# 2.net
KiCad netlist of a schematic drawn in Altium Designer
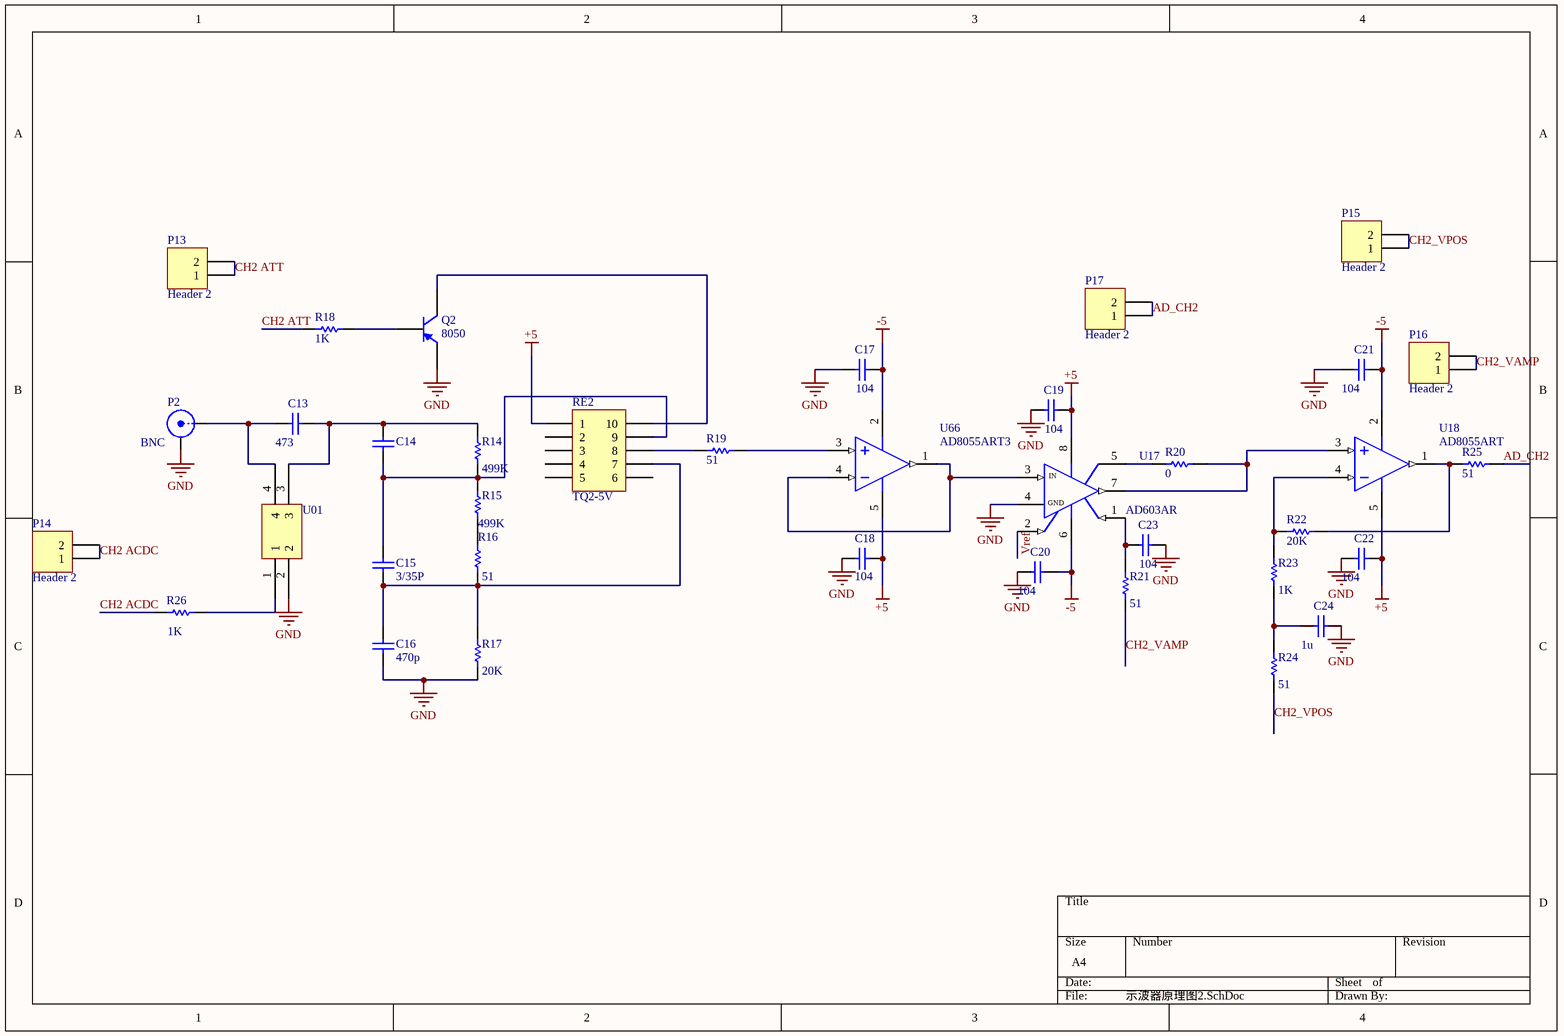
[diagram p0: 示波器原理图2.SchDoc]

(export (version "E")
  (design (tool "Eeschema 10.0.6"))
  (components
    (comp (ref "C13")
      (value "473")
      (footprint "0805封装:PCBComponent_1")
      (description "Capacitor")
      (fields (field (name "PUBLISHER") "Altium Limited"))
      (libsource (lib "Miscellaneous Devices") (part "Cap"))
    )
    (comp (ref "C14")
      (value "~")
      (footprint "0805封装:PCBComponent_1")
      (description "Capacitor")
      (fields (field (name "PUBLISHER") "Altium Limited"))
      (libsource (lib "Miscellaneous Devices") (part "Cap"))
    )
    (comp (ref "C15")
      (value "3/35P")
      (footprint "0805封装:PCBComponent_1")
      (description "Capacitor")
      (fields (field (name "PUBLISHER") "Altium Limited"))
      (libsource (lib "Miscellaneous Devices") (part "Cap"))
    )
    (comp (ref "C16")
      (value "470p")
      (footprint "0805封装:PCBComponent_1")
      (description "Capacitor")
      (fields (field (name "PUBLISHER") "Altium Limited"))
      (libsource (lib "Miscellaneous Devices") (part "Cap"))
    )
    (comp (ref "C17")
      (value "104")
      (footprint "0805封装:PCBComponent_1")
      (description "Capacitor")
      (fields (field (name "PUBLISHER") "Altium Limited"))
      (libsource (lib "Miscellaneous Devices") (part "Cap"))
    )
    (comp (ref "C18")
      (value "104")
      (footprint "0805封装:PCBComponent_1")
      (description "Capacitor")
      (fields (field (name "PUBLISHER") "Altium Limited"))
      (libsource (lib "Miscellaneous Devices") (part "Cap"))
    )
    (comp (ref "C19")
      (value "104")
      (footprint "0805封装:PCBComponent_1")
      (description "Capacitor")
      (fields (field (name "PUBLISHER") "Altium Limited"))
      (libsource (lib "Miscellaneous Devices") (part "Cap"))
    )
    (comp (ref "C20")
      (value "104")
      (footprint "0805封装:PCBComponent_1")
      (description "Capacitor")
      (fields (field (name "PUBLISHER") "Altium Limited"))
      (libsource (lib "Miscellaneous Devices") (part "Cap"))
    )
    (comp (ref "C21")
      (value "104")
      (footprint "0805封装:PCBComponent_1")
      (description "Capacitor")
      (fields (field (name "PUBLISHER") "Altium Limited"))
      (libsource (lib "Miscellaneous Devices") (part "Cap"))
    )
    (comp (ref "C22")
      (value "104")
      (footprint "0805封装:PCBComponent_1")
      (description "Capacitor")
      (fields (field (name "PUBLISHER") "Altium Limited"))
      (libsource (lib "Miscellaneous Devices") (part "Cap"))
    )
    (comp (ref "C23")
      (value "104")
      (footprint "0805封装:PCBComponent_1")
      (description "Capacitor")
      (fields (field (name "PUBLISHER") "Altium Limited"))
      (libsource (lib "Miscellaneous Devices") (part "Cap"))
    )
    (comp (ref "C24")
      (value "1u")
      (footprint "0805封装:PCBComponent_1")
      (description "Capacitor")
      (fields (field (name "PUBLISHER") "Altium Limited"))
      (libsource (lib "Miscellaneous Devices") (part "Cap"))
    )
    (comp (ref "P2")
      (value "BNC")
      (footprint "BNC_RA CON")
      (description "BNC Elbow Connector")
      (fields (field (name "PUBLISHER") "Altium Limited"))
      (libsource (lib "Miscellaneous Connectors") (part "BNC"))
    )
    (comp (ref "P13")
      (value "Header 2")
      (footprint "HDR1X2")
      (description "Header, 2-Pin")
      (fields (field (name "PUBLISHER") "Altium Limited"))
      (libsource (lib "Miscellaneous Connectors") (part "Header 2"))
    )
    (comp (ref "P14")
      (value "Header 2")
      (footprint "HDR1X2")
      (description "Header, 2-Pin")
      (fields (field (name "PUBLISHER") "Altium Limited"))
      (libsource (lib "Miscellaneous Connectors") (part "Header 2"))
    )
    (comp (ref "P15")
      (value "Header 2")
      (footprint "HDR1X2")
      (description "Header, 2-Pin")
      (fields (field (name "PUBLISHER") "Altium Limited"))
      (libsource (lib "Miscellaneous Connectors") (part "Header 2"))
    )
    (comp (ref "P16")
      (value "Header 2")
      (footprint "HDR1X2")
      (description "Header, 2-Pin")
      (fields (field (name "PUBLISHER") "Altium Limited"))
      (libsource (lib "Miscellaneous Connectors") (part "Header 2"))
    )
    (comp (ref "P17")
      (value "Header 2")
      (footprint "HDR1X2")
      (description "Header, 2-Pin")
      (fields (field (name "PUBLISHER") "Altium Limited"))
      (libsource (lib "Miscellaneous Connectors") (part "Header 2"))
    )
    (comp (ref "Q2")
      (value "8050")
      (footprint "三极管贴片:PCBComponent_1")
      (description "PNP General Purpose Amplifier")
      (fields (field (name "PUBLISHER") "Altium Limited"))
      (libsource (lib "Miscellaneous Devices") (part "2N3906"))
    )
    (comp (ref "R14")
      (value "499K")
      (footprint "0805封装:PCBComponent_1")
      (description "Resistor")
      (fields (field (name "PUBLISHER") "Altium Limited"))
      (libsource (lib "Miscellaneous Devices") (part "Res1"))
    )
    (comp (ref "R15")
      (value "499K")
      (footprint "0805封装:PCBComponent_1")
      (description "Resistor")
      (fields (field (name "PUBLISHER") "Altium Limited"))
      (libsource (lib "Miscellaneous Devices") (part "Res1"))
    )
    (comp (ref "R16")
      (value "51")
      (footprint "0805封装:PCBComponent_1")
      (description "Resistor")
      (fields (field (name "PUBLISHER") "Altium Limited"))
      (libsource (lib "Miscellaneous Devices") (part "Res1"))
    )
    (comp (ref "R17")
      (value "20K")
      (footprint "2012[0805]")
      (description "Semiconductor Resistor")
      (fields (field (name "PUBLISHER") "Altium Limited"))
      (libsource (lib "Miscellaneous Devices") (part "Res Semi"))
    )
    (comp (ref "R18")
      (value "1K")
      (footprint "0805封装:PCBComponent_1")
      (description "Resistor")
      (fields (field (name "PUBLISHER") "Altium Limited"))
      (libsource (lib "Miscellaneous Devices") (part "Res1"))
    )
    (comp (ref "R19")
      (value "51")
      (footprint "0805封装:PCBComponent_1")
      (description "Resistor")
      (fields (field (name "PUBLISHER") "Altium Limited"))
      (libsource (lib "Miscellaneous Devices") (part "Res1"))
    )
    (comp (ref "R20")
      (value "0")
      (footprint "2012[0805]")
      (description "Semiconductor Resistor")
      (fields (field (name "PUBLISHER") "Altium Limited"))
      (libsource (lib "Miscellaneous Devices") (part "Res Semi"))
    )
    (comp (ref "R21")
      (value "51")
      (footprint "2012[0805]")
      (description "Semiconductor Resistor")
      (fields (field (name "PUBLISHER") "Altium Limited"))
      (libsource (lib "Miscellaneous Devices") (part "Res Semi"))
    )
    (comp (ref "R22")
      (value "20K")
      (footprint "2012[0805]")
      (description "Semiconductor Resistor")
      (fields (field (name "PUBLISHER") "Altium Limited"))
      (libsource (lib "Miscellaneous Devices") (part "Res Semi"))
    )
    (comp (ref "R23")
      (value "1K")
      (footprint "2012[0805]")
      (description "Semiconductor Resistor")
      (fields (field (name "PUBLISHER") "Altium Limited"))
      (libsource (lib "Miscellaneous Devices") (part "Res Semi"))
    )
    (comp (ref "R24")
      (value "51")
      (footprint "2012[0805]")
      (description "Semiconductor Resistor")
      (fields (field (name "PUBLISHER") "Altium Limited"))
      (libsource (lib "Miscellaneous Devices") (part "Res Semi"))
    )
    (comp (ref "R25")
      (value "51")
      (footprint "2012[0805]")
      (description "Semiconductor Resistor")
      (fields (field (name "PUBLISHER") "Altium Limited"))
      (libsource (lib "Miscellaneous Devices") (part "Res Semi"))
    )
    (comp (ref "R26")
      (value "1K")
      (footprint "0805封装:PCBComponent_1")
      (description "Resistor")
      (fields (field (name "PUBLISHER") "Altium Limited"))
      (libsource (lib "Miscellaneous Devices") (part "Res1"))
    )
    (comp (ref "RE2")
      (value "TQ2-5V")
      (footprint "PcbLib1:PCBComponent_1")
      (libsource (lib "TQ2-5V") (part "Component_1"))
    )
    (comp (ref "U01")
      (value "~")
      (footprint "SOP254P610X218-4N")
      (libsource (lib "AQY210E") (part "Component_1"))
    )
    (comp (ref "U17")
      (value "AD603AR")
      (footprint "SOIC127P600X175-8N")
      (description "Low-Noise, 90MHz Variable Gain Amplifier")
      (libsource (lib "AD Variable Gain Amplifier Sch") (part "AD603AR"))
    )
    (comp (ref "U18")
      (value "AD8055ART")
      (footprint "SOT95P245X110-5N")
      (description "Low Cost, 300MHz Voltage Feedback Amplifier")
      (libsource (lib "AD Operational Amplifier Sch") (part "AD8055ART"))
    )
    (comp (ref "U66")
      (value "AD8055ART3")
      (footprint "SOT95P245X110-5N")
      (description "Low Cost, 300MHz Voltage Feedback Amplifier")
      (libsource (lib "AD Operational Amplifier Sch") (part "AD8055ART"))
    )
  )
  (nets
    (net (code "1") (name "+5") (class "Default")
      (node (ref "C18") (pin "1") (pinfunction "1_1") (pintype "passive"))
      (node (ref "C19") (pin "2") (pinfunction "2_2") (pintype "passive"))
      (node (ref "C22") (pin "2") (pinfunction "2_2") (pintype "passive"))
      (node (ref "RE2") (pin "1") (pinfunction "1_1") (pintype "passive"))
      (node (ref "U17") (pin "8") (pinfunction "V+_8") (pintype "power_in"))
      (node (ref "U18") (pin "5") (pinfunction "V+_5") (pintype "power_in"))
      (node (ref "U66") (pin "5") (pinfunction "V+_5") (pintype "power_in"))
    )
    (net (code "2") (name "-5") (class "Default")
      (node (ref "C17") (pin "1") (pinfunction "1_1") (pintype "passive"))
      (node (ref "C20") (pin "2") (pinfunction "2_2") (pintype "passive"))
      (node (ref "C21") (pin "2") (pinfunction "2_2") (pintype "passive"))
      (node (ref "U17") (pin "6") (pinfunction "V-_6") (pintype "power_in"))
      (node (ref "U18") (pin "2") (pinfunction "V-_2") (pintype "power_in"))
      (node (ref "U66") (pin "2") (pinfunction "V-_2") (pintype "power_in"))
    )
    (net (code "3") (name "/AD_CH2") (class "Default")
      (node (ref "P17") (pin "1") (pinfunction "1_1") (pintype "passive"))
      (node (ref "P17") (pin "2") (pinfunction "2_2") (pintype "passive"))
      (node (ref "R25") (pin "1") (pinfunction "1_1") (pintype "passive"))
    )
    (net (code "4") (name "/CH2 ACDC") (class "Default")
      (node (ref "P14") (pin "1") (pinfunction "1_1") (pintype "passive"))
      (node (ref "P14") (pin "2") (pinfunction "2_2") (pintype "passive"))
      (node (ref "R26") (pin "1") (pinfunction "1_1") (pintype "passive"))
    )
    (net (code "5") (name "/CH2 ATT") (class "Default")
      (node (ref "P13") (pin "1") (pinfunction "1_1") (pintype "passive"))
      (node (ref "P13") (pin "2") (pinfunction "2_2") (pintype "passive"))
      (node (ref "R18") (pin "2") (pinfunction "2_2") (pintype "passive"))
    )
    (net (code "6") (name "/CH2_VAMP") (class "Default")
      (node (ref "P16") (pin "1") (pinfunction "1_1") (pintype "passive"))
      (node (ref "P16") (pin "2") (pinfunction "2_2") (pintype "passive"))
      (node (ref "R21") (pin "1") (pinfunction "1_1") (pintype "passive"))
    )
    (net (code "7") (name "/CH2_VPOS") (class "Default")
      (node (ref "P15") (pin "1") (pinfunction "1_1") (pintype "passive"))
      (node (ref "P15") (pin "2") (pinfunction "2_2") (pintype "passive"))
      (node (ref "R24") (pin "1") (pinfunction "1_1") (pintype "passive"))
    )
    (net (code "8") (name "/Vref") (class "Default")
      (node (ref "U17") (pin "2") (pinfunction "G-_2") (pintype "input"))
    )
    (net (code "9") (name "GND") (class "Default")
      (node (ref "C16") (pin "1") (pinfunction "1_1") (pintype "passive"))
      (node (ref "C17") (pin "2") (pinfunction "2_2") (pintype "passive"))
      (node (ref "C18") (pin "2") (pinfunction "2_2") (pintype "passive"))
      (node (ref "C19") (pin "1") (pinfunction "1_1") (pintype "passive"))
      (node (ref "C20") (pin "1") (pinfunction "1_1") (pintype "passive"))
      (node (ref "C21") (pin "1") (pinfunction "1_1") (pintype "passive"))
      (node (ref "C22") (pin "1") (pinfunction "1_1") (pintype "passive"))
      (node (ref "C23") (pin "2") (pinfunction "2_2") (pintype "passive"))
      (node (ref "C24") (pin "2") (pinfunction "2_2") (pintype "passive"))
      (node (ref "P2") (pin "2") (pinfunction "Y_2") (pintype "passive"))
      (node (ref "Q2") (pin "1") (pinfunction "E_1") (pintype "passive"))
      (node (ref "R17") (pin "1") (pinfunction "1_1") (pintype "passive"))
      (node (ref "U01") (pin "2") (pinfunction "2_2") (pintype "passive"))
      (node (ref "U17") (pin "4") (pinfunction "COMM_4") (pintype "power_in"))
    )
    (net (code "10") (name "Net-(C13-Pad2)") (class "Default")
      (node (ref "C13") (pin "2") (pinfunction "2_2") (pintype "passive"))
      (node (ref "C14") (pin "2") (pinfunction "2_2") (pintype "passive"))
      (node (ref "R14") (pin "2") (pinfunction "2_2") (pintype "passive"))
      (node (ref "U01") (pin "3") (pinfunction "3_3") (pintype "passive"))
    )
    (net (code "11") (name "Net-(C14-Pad1)") (class "Default")
      (node (ref "C14") (pin "1") (pinfunction "1_1") (pintype "passive"))
      (node (ref "C15") (pin "2") (pinfunction "2_2") (pintype "passive"))
      (node (ref "R14") (pin "1") (pinfunction "1_1") (pintype "passive"))
      (node (ref "R15") (pin "2") (pinfunction "2_2") (pintype "passive"))
      (node (ref "RE2") (pin "9") (pinfunction "9_9") (pintype "passive"))
    )
    (net (code "12") (name "Net-(C15-Pad1)") (class "Default")
      (node (ref "C15") (pin "1") (pinfunction "1_1") (pintype "passive"))
      (node (ref "C16") (pin "2") (pinfunction "2_2") (pintype "passive"))
      (node (ref "R16") (pin "1") (pinfunction "1_1") (pintype "passive"))
      (node (ref "R17") (pin "2") (pinfunction "2_2") (pintype "passive"))
      (node (ref "RE2") (pin "7") (pinfunction "7_7") (pintype "passive"))
    )
    (net (code "13") (name "Net-(C24-Pad1)") (class "Default")
      (node (ref "C24") (pin "1") (pinfunction "1_1") (pintype "passive"))
      (node (ref "R23") (pin "1") (pinfunction "1_1") (pintype "passive"))
      (node (ref "R24") (pin "2") (pinfunction "2_2") (pintype "passive"))
    )
    (net (code "14") (name "Net-(P2-X)") (class "Default")
      (node (ref "C13") (pin "1") (pinfunction "1_1") (pintype "passive"))
      (node (ref "P2") (pin "1") (pinfunction "X_1") (pintype "passive"))
      (node (ref "U01") (pin "4") (pinfunction "4_4") (pintype "passive"))
    )
    (net (code "15") (name "Net-(Q2-B)") (class "Default")
      (node (ref "Q2") (pin "2") (pinfunction "B_2") (pintype "passive"))
      (node (ref "R18") (pin "1") (pinfunction "1_1") (pintype "passive"))
    )
    (net (code "16") (name "Net-(Q2-C)") (class "Default")
      (node (ref "Q2") (pin "3") (pinfunction "C_3") (pintype "passive"))
      (node (ref "RE2") (pin "10") (pinfunction "10_10") (pintype "passive"))
    )
    (net (code "17") (name "Net-(R15-Pad1)") (class "Default")
      (node (ref "R15") (pin "1") (pinfunction "1_1") (pintype "passive"))
      (node (ref "R16") (pin "2") (pinfunction "2_2") (pintype "passive"))
    )
    (net (code "18") (name "Net-(R19-Pad2)") (class "Default")
      (node (ref "R19") (pin "2") (pinfunction "2_2") (pintype "passive"))
      (node (ref "RE2") (pin "8") (pinfunction "8_8") (pintype "passive"))
    )
    (net (code "19") (name "Net-(R26-Pad2)") (class "Default")
      (node (ref "R26") (pin "2") (pinfunction "2_2") (pintype "passive"))
      (node (ref "U01") (pin "1") (pinfunction "1_1") (pintype "passive"))
    )
    (net (code "20") (name "Net-(U17-FDBK)") (class "Default")
      (node (ref "R20") (pin "2") (pinfunction "2_2") (pintype "passive"))
      (node (ref "U17") (pin "5") (pinfunction "FDBK_5") (pintype "passive"))
    )
    (net (code "21") (name "Net-(U17-G+)") (class "Default")
      (node (ref "C23") (pin "1") (pinfunction "1_1") (pintype "passive"))
      (node (ref "R21") (pin "2") (pinfunction "2_2") (pintype "passive"))
      (node (ref "U17") (pin "1") (pinfunction "G+_1") (pintype "input"))
    )
    (net (code "22") (name "Net-(U17-VINP)") (class "Default")
      (node (ref "U17") (pin "3") (pinfunction "VINP_3") (pintype "input"))
      (node (ref "U66") (pin "1") (pinfunction "OUT_1") (pintype "output"))
      (node (ref "U66") (pin "4") (pinfunction "IN-_4") (pintype "input"))
    )
    (net (code "23") (name "Net-(U17-VOUT)") (class "Default")
      (node (ref "R20") (pin "1") (pinfunction "1_1") (pintype "passive"))
      (node (ref "U17") (pin "7") (pinfunction "VOUT_7") (pintype "output"))
      (node (ref "U18") (pin "3") (pinfunction "IN+_3") (pintype "input"))
    )
    (net (code "24") (name "Net-(U18-IN-)") (class "Default")
      (node (ref "R22") (pin "2") (pinfunction "2_2") (pintype "passive"))
      (node (ref "R23") (pin "2") (pinfunction "2_2") (pintype "passive"))
      (node (ref "U18") (pin "4") (pinfunction "IN-_4") (pintype "input"))
    )
    (net (code "25") (name "Net-(U18-OUT)") (class "Default")
      (node (ref "R22") (pin "1") (pinfunction "1_1") (pintype "passive"))
      (node (ref "R25") (pin "2") (pinfunction "2_2") (pintype "passive"))
      (node (ref "U18") (pin "1") (pinfunction "OUT_1") (pintype "output"))
    )
    (net (code "26") (name "Net-(U66-IN+)") (class "Default")
      (node (ref "R19") (pin "1") (pinfunction "1_1") (pintype "passive"))
      (node (ref "U66") (pin "3") (pinfunction "IN+_3") (pintype "input"))
    )
    (net (code "27") (name "unconnected-(RE2-Pad2)") (class "Default")
      (node (ref "RE2") (pin "2") (pinfunction "2_2") (pintype "passive"))
    )
    (net (code "28") (name "unconnected-(RE2-Pad3)") (class "Default")
      (node (ref "RE2") (pin "3") (pinfunction "3_3") (pintype "passive"))
    )
    (net (code "29") (name "unconnected-(RE2-Pad4)") (class "Default")
      (node (ref "RE2") (pin "4") (pinfunction "4_4") (pintype "passive"))
    )
    (net (code "30") (name "unconnected-(RE2-Pad5)") (class "Default")
      (node (ref "RE2") (pin "5") (pinfunction "5_5") (pintype "passive"))
    )
    (net (code "31") (name "unconnected-(RE2-Pad6)") (class "Default")
      (node (ref "RE2") (pin "6") (pinfunction "6_6") (pintype "passive"))
    )
  )
)
